# maxTouch-EXT_V1.net
KiCad netlist of a schematic drawn in EAGLE
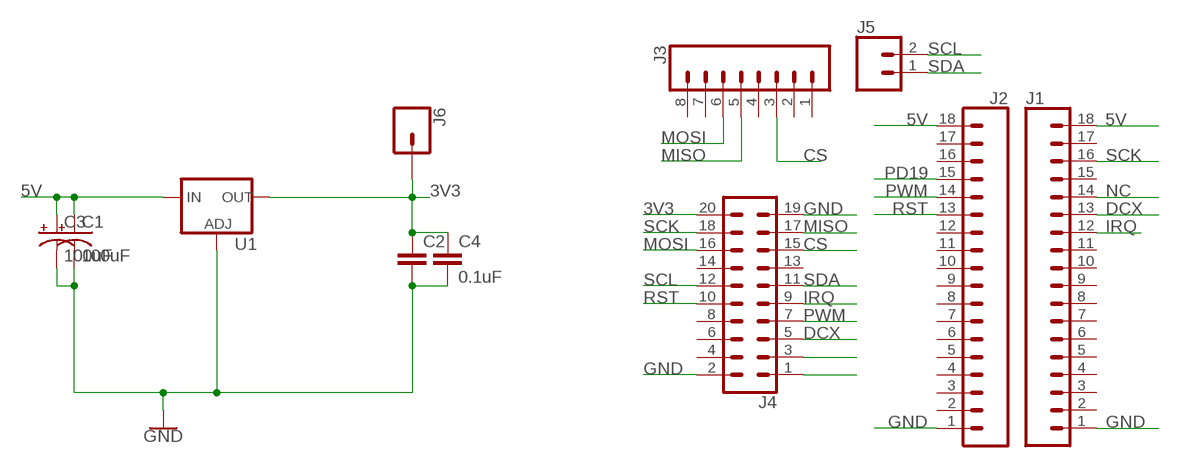
[diagram p0: schematic, sheet 1]

(export (version "E")
  (design (tool "Eeschema 10.0.6"))
  (components
    (comp (ref "C1")
      (value "100uF")
      (footprint "eagle-import:NIC_10X10.5_CAP")
      (libsource (lib "eagle-import") (part "100UF-POLAR-10X10.5-63V-20%"))
    )
    (comp (ref "C2")
      (value "10uF")
      (footprint "eagle-import:0805")
      (libsource (lib "eagle-import") (part "CAP-0805"))
    )
    (comp (ref "C3")
      (value "100uF")
      (footprint "eagle-import:CPOL-RADIAL-2.5MM-6.5MM")
      (libsource (lib "eagle-import") (part "100UF-POLAR-RADIAL-2.5MM-25V-20%"))
    )
    (comp (ref "C4")
      (value "0.1uF")
      (footprint "eagle-import:CAP-PTH-SMALL-KIT")
      (libsource (lib "eagle-import") (part "0.1UF-KIT-EZ-50V-20%"))
    )
    (comp (ref "J1")
      (value "CONN_18SILK")
      (footprint "eagle-import:1X18")
      (libsource (lib "eagle-import") (part "CONN_18SILK"))
    )
    (comp (ref "J2")
      (value "CONN_18SILK")
      (footprint "eagle-import:1X18")
      (libsource (lib "eagle-import") (part "CONN_18SILK"))
    )
    (comp (ref "J3")
      (value "CONN_08\"")
      (footprint "eagle-import:1X08")
      (libsource (lib "eagle-import") (part "CONN_08{dblquote}"))
    )
    (comp (ref "J4")
      (value "CONN_10X2")
      (footprint "eagle-import:2X10")
      (libsource (lib "eagle-import") (part "CONN_10X2"))
    )
    (comp (ref "J5")
      (value "CONN_02")
      (footprint "eagle-import:1X02")
      (libsource (lib "eagle-import") (part "CONN_02"))
    )
    (comp (ref "J6")
      (value "CONN_01")
      (footprint "eagle-import:1X01")
      (libsource (lib "eagle-import") (part "CONN_01"))
    )
    (comp (ref "U1")
      (value "V_REG_LM1117SOT223")
      (footprint "eagle-import:SOT223")
      (libsource (lib "eagle-import") (part "V_REG_LM1117SOT223"))
    )
  )
  (nets
    (net (code "1") (name "/3V3") (class "Default")
      (node (ref "C2") (pin "1") (pinfunction "1_1") (pintype "passive"))
      (node (ref "C4") (pin "1") (pinfunction "1_1") (pintype "passive"))
      (node (ref "J4") (pin "20") (pinfunction "20_20") (pintype "passive"))
      (node (ref "J6") (pin "1") (pinfunction "1_1") (pintype "passive"))
      (node (ref "U1") (pin "2") (pinfunction "OUT_2") (pintype "output"))
      (node (ref "U1") (pin "4") (pinfunction "OUT_4") (pintype "output"))
    )
    (net (code "2") (name "/5V") (class "Default")
      (node (ref "C1") (pin "+") (pinfunction "+_+") (pintype "passive"))
      (node (ref "C3") (pin "1") (pinfunction "+_1") (pintype "passive"))
      (node (ref "J1") (pin "18") (pinfunction "18_18") (pintype "passive"))
      (node (ref "J2") (pin "18") (pinfunction "18_18") (pintype "passive"))
      (node (ref "U1") (pin "3") (pinfunction "IN_3") (pintype "input"))
    )
    (net (code "3") (name "/CS") (class "Default")
      (node (ref "J3") (pin "3") (pinfunction "3_3") (pintype "passive"))
      (node (ref "J4") (pin "15") (pinfunction "15_15") (pintype "passive"))
    )
    (net (code "4") (name "/DCX") (class "Default")
      (node (ref "J1") (pin "13") (pinfunction "13_13") (pintype "passive"))
      (node (ref "J4") (pin "5") (pinfunction "5_5") (pintype "passive"))
    )
    (net (code "5") (name "/IRQ") (class "Default")
      (node (ref "J1") (pin "12") (pinfunction "12_12") (pintype "passive"))
      (node (ref "J4") (pin "9") (pinfunction "9_9") (pintype "passive"))
    )
    (net (code "6") (name "/MISO") (class "Default")
      (node (ref "J3") (pin "5") (pinfunction "5_5") (pintype "passive"))
      (node (ref "J4") (pin "17") (pinfunction "17_17") (pintype "passive"))
    )
    (net (code "7") (name "/MOSI") (class "Default")
      (node (ref "J3") (pin "6") (pinfunction "6_6") (pintype "passive"))
      (node (ref "J4") (pin "16") (pinfunction "16_16") (pintype "passive"))
    )
    (net (code "8") (name "/NC") (class "Default")
      (node (ref "J1") (pin "14") (pinfunction "14_14") (pintype "passive"))
    )
    (net (code "9") (name "/PD19") (class "Default")
      (node (ref "J2") (pin "15") (pinfunction "15_15") (pintype "passive"))
    )
    (net (code "10") (name "/PWM") (class "Default")
      (node (ref "J2") (pin "14") (pinfunction "14_14") (pintype "passive"))
      (node (ref "J4") (pin "7") (pinfunction "7_7") (pintype "passive"))
    )
    (net (code "11") (name "/RST") (class "Default")
      (node (ref "J2") (pin "13") (pinfunction "13_13") (pintype "passive"))
      (node (ref "J4") (pin "10") (pinfunction "10_10") (pintype "passive"))
    )
    (net (code "12") (name "/SCK") (class "Default")
      (node (ref "J1") (pin "16") (pinfunction "16_16") (pintype "passive"))
      (node (ref "J4") (pin "18") (pinfunction "18_18") (pintype "passive"))
    )
    (net (code "13") (name "/SCL") (class "Default")
      (node (ref "J4") (pin "12") (pinfunction "12_12") (pintype "passive"))
      (node (ref "J5") (pin "2") (pinfunction "2_2") (pintype "passive"))
    )
    (net (code "14") (name "/SDA") (class "Default")
      (node (ref "J4") (pin "11") (pinfunction "11_11") (pintype "passive"))
      (node (ref "J5") (pin "1") (pinfunction "1_1") (pintype "passive"))
    )
    (net (code "15") (name "GND") (class "Default")
      (node (ref "C1") (pin "-") (pinfunction "-_-") (pintype "passive"))
      (node (ref "C2") (pin "2") (pinfunction "2_2") (pintype "passive"))
      (node (ref "C3") (pin "2") (pinfunction "-_2") (pintype "passive"))
      (node (ref "C4") (pin "2") (pinfunction "2_2") (pintype "passive"))
      (node (ref "J1") (pin "1") (pinfunction "1_1") (pintype "passive"))
      (node (ref "J2") (pin "1") (pinfunction "1_1") (pintype "passive"))
      (node (ref "J4") (pin "19") (pinfunction "19_19") (pintype "passive"))
      (node (ref "J4") (pin "2") (pinfunction "2_2") (pintype "passive"))
      (node (ref "U1") (pin "1") (pinfunction "ADJ_1") (pintype "input"))
    )
    (net (code "16") (name "unconnected-(J1-Pad2)") (class "Default")
      (node (ref "J1") (pin "2") (pinfunction "2_2") (pintype "passive"))
    )
    (net (code "17") (name "unconnected-(J1-Pad3)") (class "Default")
      (node (ref "J1") (pin "3") (pinfunction "3_3") (pintype "passive"))
    )
    (net (code "18") (name "unconnected-(J1-Pad4)") (class "Default")
      (node (ref "J1") (pin "4") (pinfunction "4_4") (pintype "passive"))
    )
    (net (code "19") (name "unconnected-(J1-Pad5)") (class "Default")
      (node (ref "J1") (pin "5") (pinfunction "5_5") (pintype "passive"))
    )
    (net (code "20") (name "unconnected-(J1-Pad6)") (class "Default")
      (node (ref "J1") (pin "6") (pinfunction "6_6") (pintype "passive"))
    )
    (net (code "21") (name "unconnected-(J1-Pad7)") (class "Default")
      (node (ref "J1") (pin "7") (pinfunction "7_7") (pintype "passive"))
    )
    (net (code "22") (name "unconnected-(J1-Pad8)") (class "Default")
      (node (ref "J1") (pin "8") (pinfunction "8_8") (pintype "passive"))
    )
    (net (code "23") (name "unconnected-(J1-Pad9)") (class "Default")
      (node (ref "J1") (pin "9") (pinfunction "9_9") (pintype "passive"))
    )
    (net (code "24") (name "unconnected-(J1-Pad10)") (class "Default")
      (node (ref "J1") (pin "10") (pinfunction "10_10") (pintype "passive"))
    )
    (net (code "25") (name "unconnected-(J1-Pad11)") (class "Default")
      (node (ref "J1") (pin "11") (pinfunction "11_11") (pintype "passive"))
    )
    (net (code "26") (name "unconnected-(J1-Pad15)") (class "Default")
      (node (ref "J1") (pin "15") (pinfunction "15_15") (pintype "passive"))
    )
    (net (code "27") (name "unconnected-(J1-Pad17)") (class "Default")
      (node (ref "J1") (pin "17") (pinfunction "17_17") (pintype "passive"))
    )
    (net (code "28") (name "unconnected-(J2-Pad2)") (class "Default")
      (node (ref "J2") (pin "2") (pinfunction "2_2") (pintype "passive"))
    )
    (net (code "29") (name "unconnected-(J2-Pad3)") (class "Default")
      (node (ref "J2") (pin "3") (pinfunction "3_3") (pintype "passive"))
    )
    (net (code "30") (name "unconnected-(J2-Pad4)") (class "Default")
      (node (ref "J2") (pin "4") (pinfunction "4_4") (pintype "passive"))
    )
    (net (code "31") (name "unconnected-(J2-Pad5)") (class "Default")
      (node (ref "J2") (pin "5") (pinfunction "5_5") (pintype "passive"))
    )
    (net (code "32") (name "unconnected-(J2-Pad6)") (class "Default")
      (node (ref "J2") (pin "6") (pinfunction "6_6") (pintype "passive"))
    )
    (net (code "33") (name "unconnected-(J2-Pad7)") (class "Default")
      (node (ref "J2") (pin "7") (pinfunction "7_7") (pintype "passive"))
    )
    (net (code "34") (name "unconnected-(J2-Pad8)") (class "Default")
      (node (ref "J2") (pin "8") (pinfunction "8_8") (pintype "passive"))
    )
    (net (code "35") (name "unconnected-(J2-Pad9)") (class "Default")
      (node (ref "J2") (pin "9") (pinfunction "9_9") (pintype "passive"))
    )
    (net (code "36") (name "unconnected-(J2-Pad10)") (class "Default")
      (node (ref "J2") (pin "10") (pinfunction "10_10") (pintype "passive"))
    )
    (net (code "37") (name "unconnected-(J2-Pad11)") (class "Default")
      (node (ref "J2") (pin "11") (pinfunction "11_11") (pintype "passive"))
    )
    (net (code "38") (name "unconnected-(J2-Pad12)") (class "Default")
      (node (ref "J2") (pin "12") (pinfunction "12_12") (pintype "passive"))
    )
    (net (code "39") (name "unconnected-(J2-Pad16)") (class "Default")
      (node (ref "J2") (pin "16") (pinfunction "16_16") (pintype "passive"))
    )
    (net (code "40") (name "unconnected-(J2-Pad17)") (class "Default")
      (node (ref "J2") (pin "17") (pinfunction "17_17") (pintype "passive"))
    )
    (net (code "41") (name "unconnected-(J3-Pad1)") (class "Default")
      (node (ref "J3") (pin "1") (pinfunction "1_1") (pintype "passive"))
    )
    (net (code "42") (name "unconnected-(J3-Pad2)") (class "Default")
      (node (ref "J3") (pin "2") (pinfunction "2_2") (pintype "passive"))
    )
    (net (code "43") (name "unconnected-(J3-Pad4)") (class "Default")
      (node (ref "J3") (pin "4") (pinfunction "4_4") (pintype "passive"))
    )
    (net (code "44") (name "unconnected-(J3-Pad7)") (class "Default")
      (node (ref "J3") (pin "7") (pinfunction "7_7") (pintype "passive"))
    )
    (net (code "45") (name "unconnected-(J3-Pad8)") (class "Default")
      (node (ref "J3") (pin "8") (pinfunction "8_8") (pintype "passive"))
    )
    (net (code "46") (name "unconnected-(J4-Pad1)") (class "Default")
      (node (ref "J4") (pin "1") (pinfunction "1_1") (pintype "passive"))
    )
    (net (code "47") (name "unconnected-(J4-Pad3)") (class "Default")
      (node (ref "J4") (pin "3") (pinfunction "3_3") (pintype "passive"))
    )
    (net (code "48") (name "unconnected-(J4-Pad4)") (class "Default")
      (node (ref "J4") (pin "4") (pinfunction "4_4") (pintype "passive"))
    )
    (net (code "49") (name "unconnected-(J4-Pad6)") (class "Default")
      (node (ref "J4") (pin "6") (pinfunction "6_6") (pintype "passive"))
    )
    (net (code "50") (name "unconnected-(J4-Pad8)") (class "Default")
      (node (ref "J4") (pin "8") (pinfunction "8_8") (pintype "passive"))
    )
    (net (code "51") (name "unconnected-(J4-Pad13)") (class "Default")
      (node (ref "J4") (pin "13") (pinfunction "13_13") (pintype "passive"))
    )
    (net (code "52") (name "unconnected-(J4-Pad14)") (class "Default")
      (node (ref "J4") (pin "14") (pinfunction "14_14") (pintype "passive"))
    )
  )
)
